# kick_line.net
KiCad netlist of a schematic drawn in EAGLE
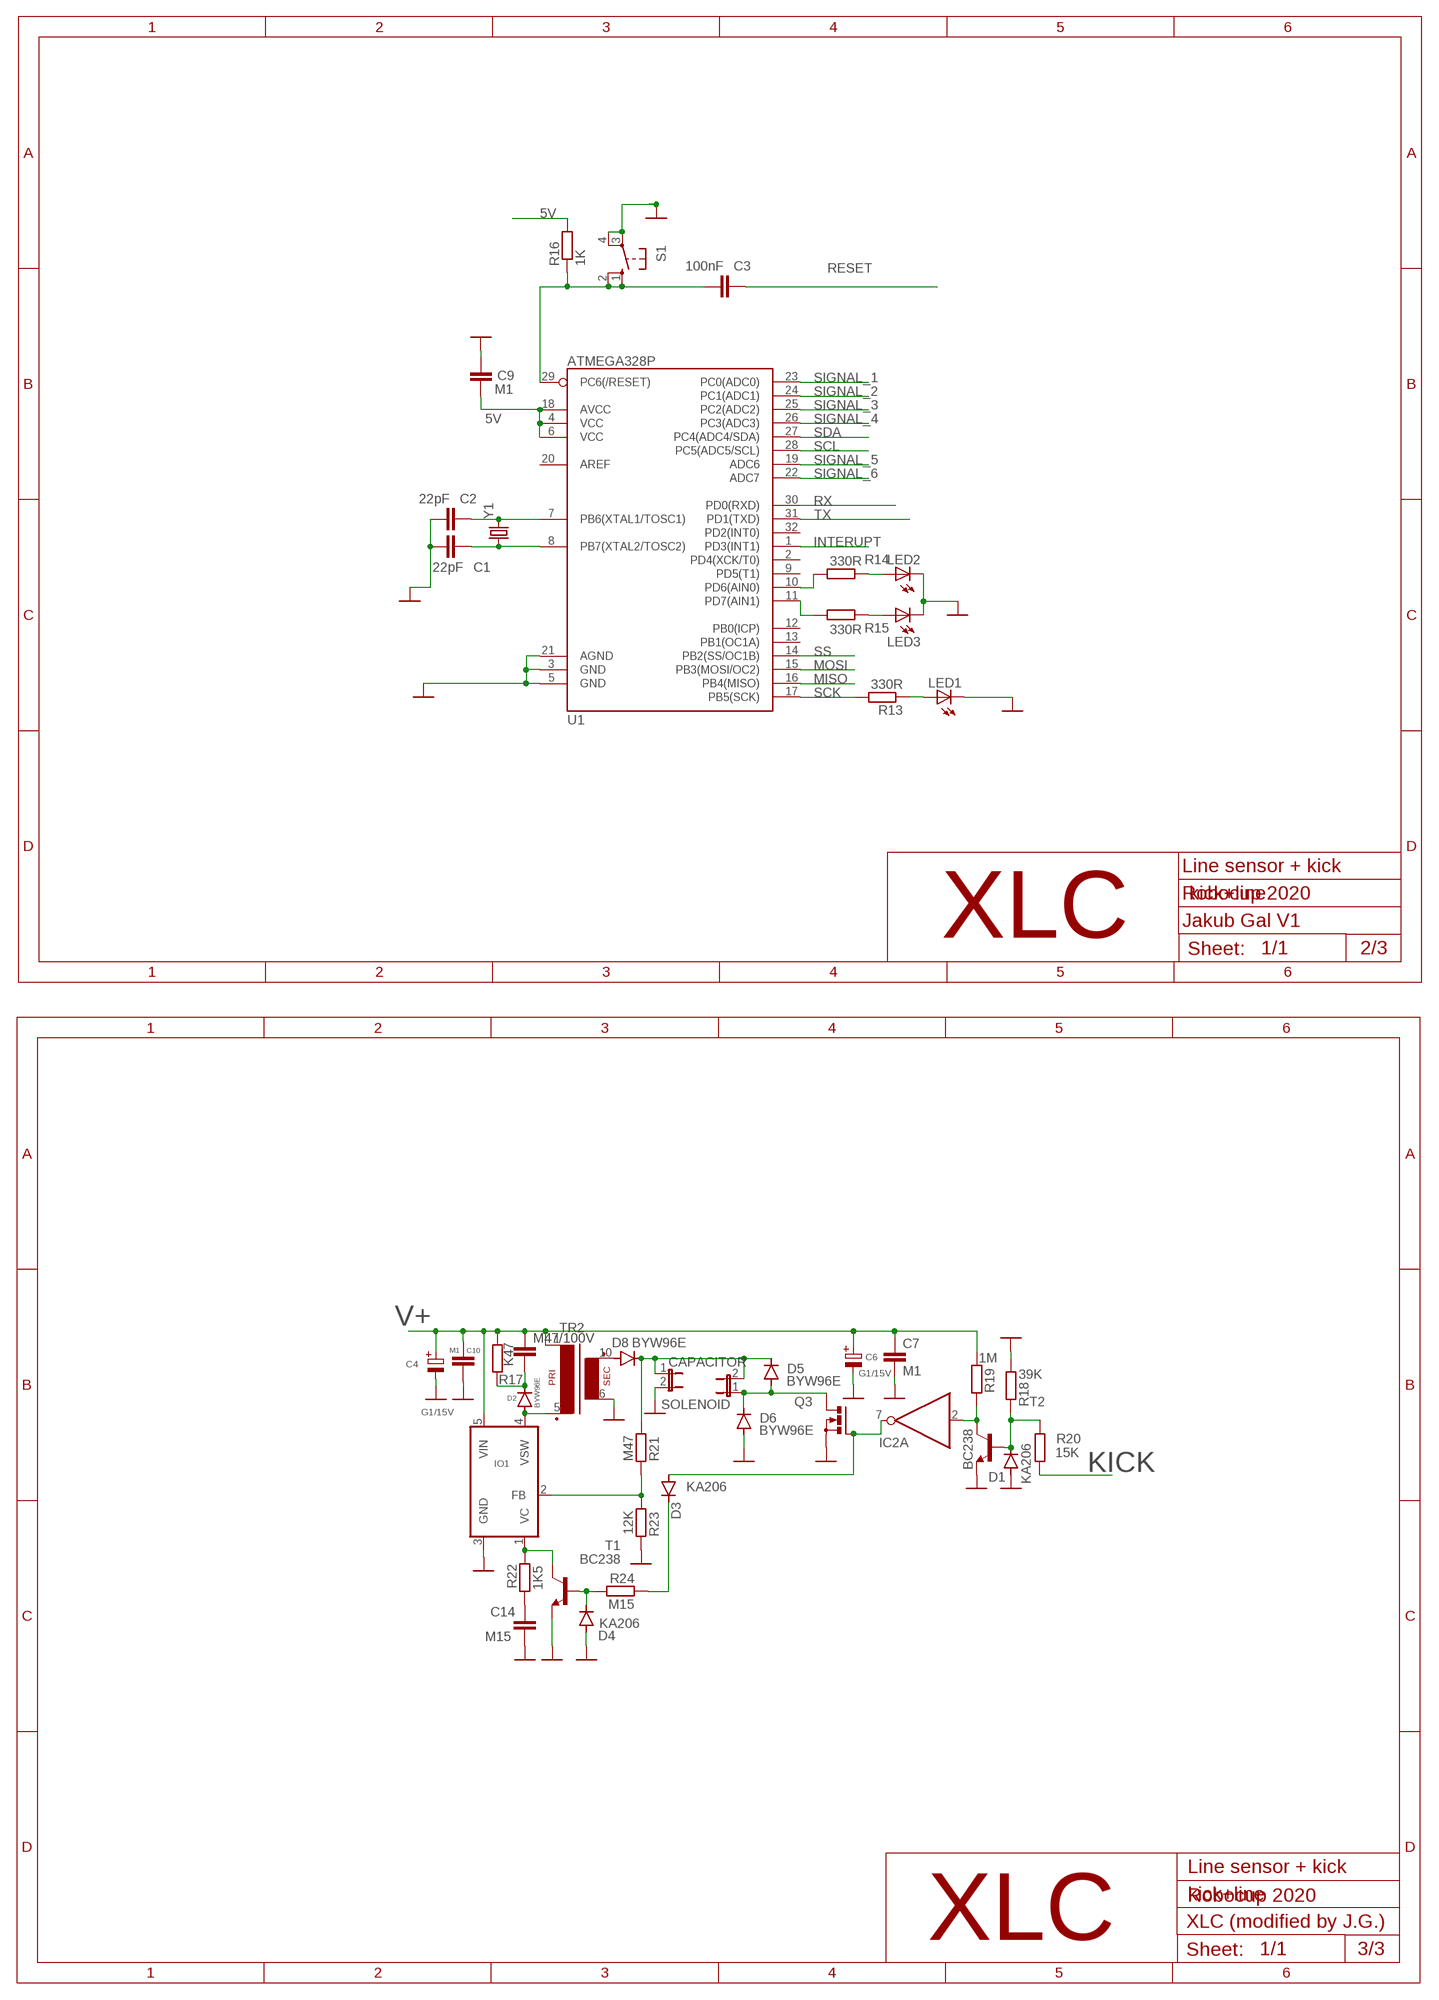
[diagram p0: schematic, sheet 1, part 1 of 2]
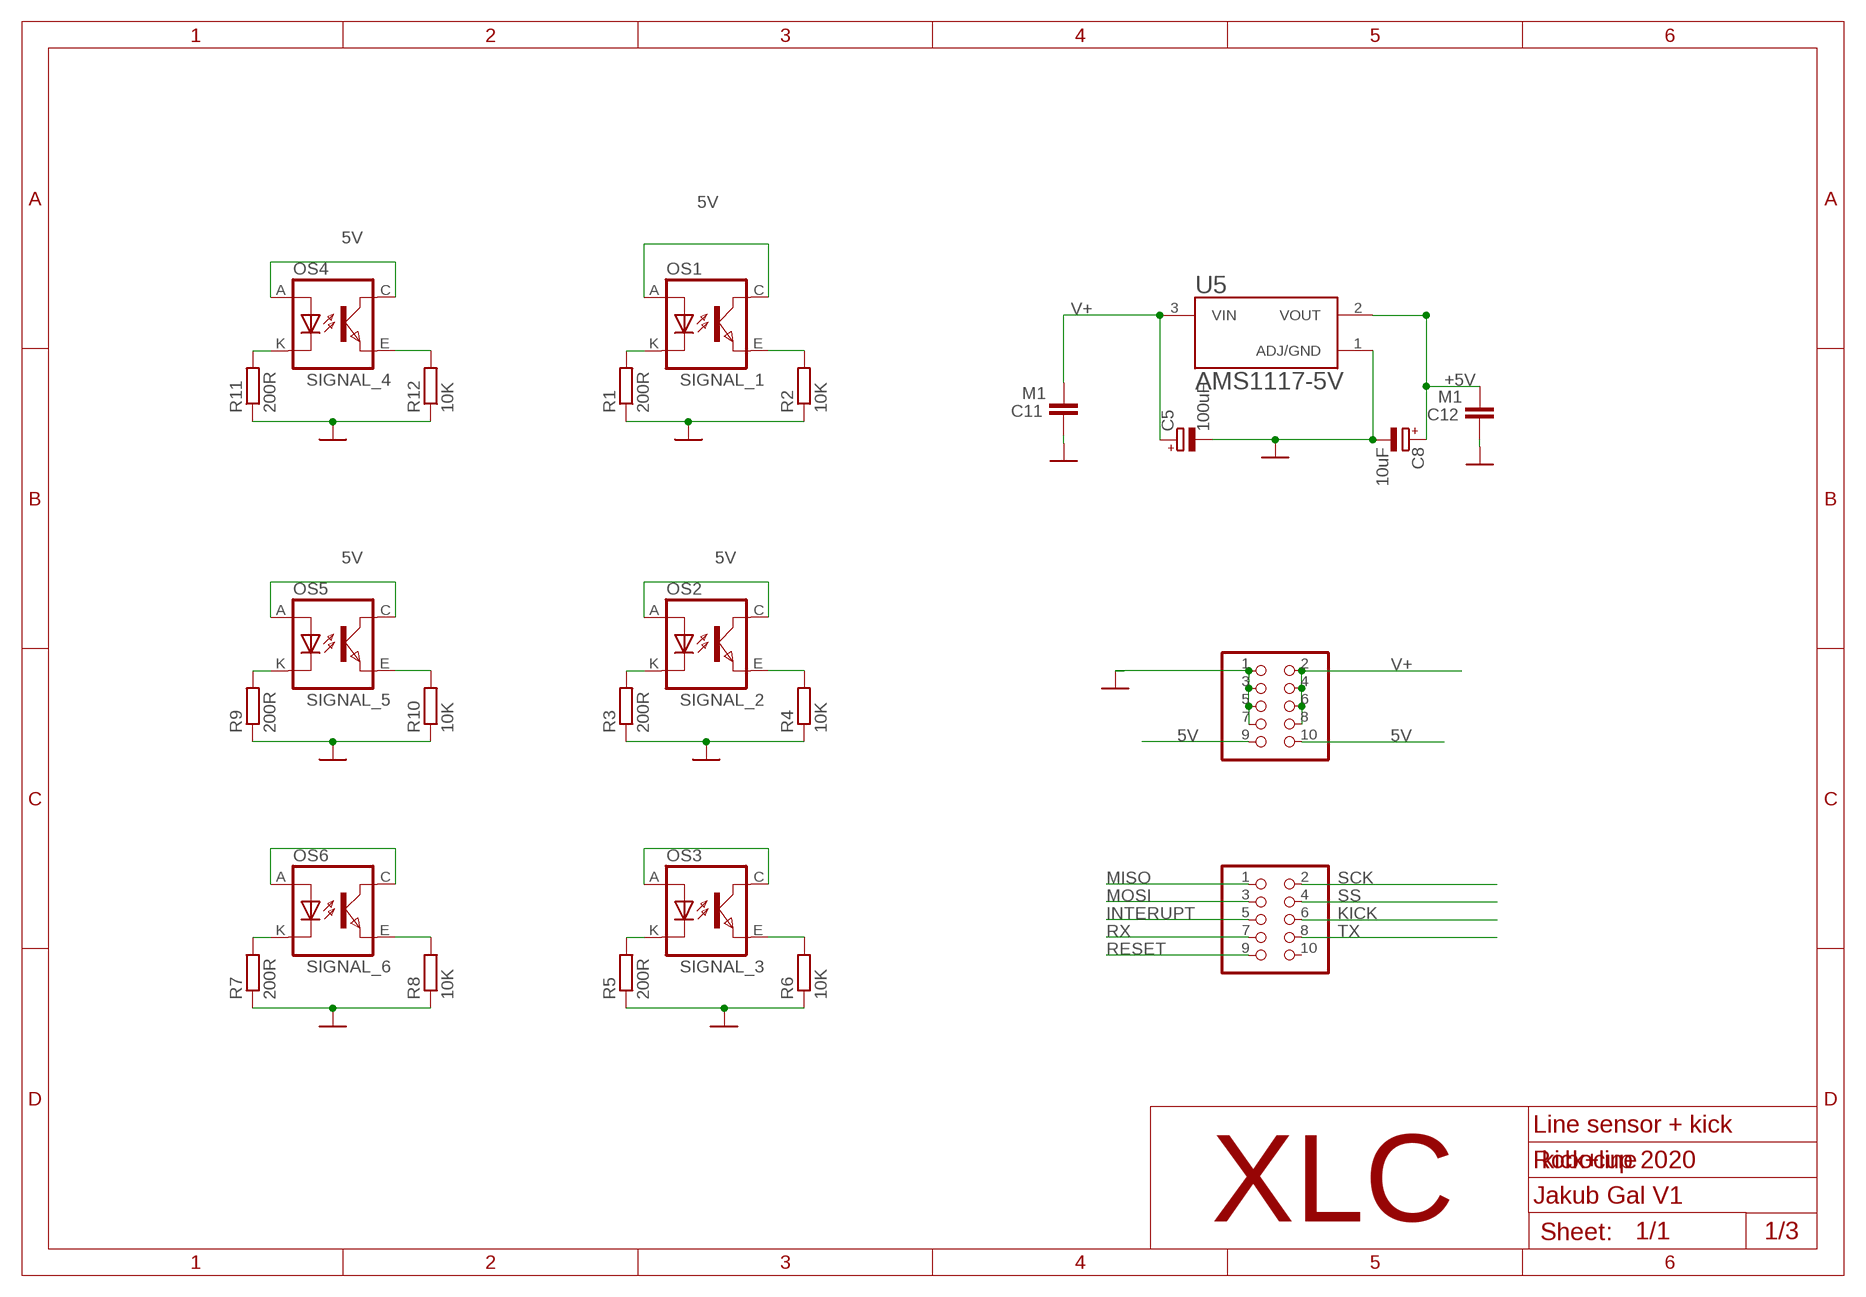
[diagram p1: schematic, sheet 1, part 2 of 2]

(export (version "E")
  (design (tool "Eeschema 10.0.6"))
  (components
    (comp (ref "C1")
      (value "22pF")
      (footprint "eagle-import:C0603")
      (libsource (lib "eagle-import") (part "C-EUC0603"))
    )
    (comp (ref "C2")
      (value "22pF")
      (footprint "eagle-import:C0603")
      (libsource (lib "eagle-import") (part "C-EUC0603"))
    )
    (comp (ref "C3")
      (value "100nF")
      (footprint "eagle-import:C0603")
      (libsource (lib "eagle-import") (part "C-EUC0603"))
    )
    (comp (ref "C4")
      (value "G1/15V")
      (footprint "eagle-import:E-2,5_7-RAD")
      (libsource (lib "eagle-import") (part "KOND-ELEKT-2,5/7"))
    )
    (comp (ref "C5")
      (value "100uF")
      (footprint "eagle-import:UD-6,3X7,7_NICHICON")
      (libsource (lib "eagle-import") (part "CPOL-EUUD-6,3X7,7"))
    )
    (comp (ref "C6")
      (value "G1/15V")
      (footprint "eagle-import:E-2,5_7-RAD")
      (libsource (lib "eagle-import") (part "KOND-ELEKT-2,5/7"))
    )
    (comp (ref "C7")
      (value "M1")
      (footprint "eagle-import:C0805K")
      (libsource (lib "eagle-import") (part "resistor_348_C-EUC0805K"))
    )
    (comp (ref "C8")
      (value "10uF")
      (footprint "eagle-import:UD-4X5,8_NICHICON")
      (libsource (lib "eagle-import") (part "CPOL-EUUD-4X5,8"))
    )
    (comp (ref "C9")
      (value "M1")
      (footprint "eagle-import:C0603")
      (libsource (lib "eagle-import") (part "C-EUC0603"))
    )
    (comp (ref "C10")
      (value "M1")
      (footprint "eagle-import:C0805K")
      (libsource (lib "eagle-import") (part "resistor_348_C-EUC0805K"))
    )
    (comp (ref "C11")
      (value "M1")
      (footprint "eagle-import:C0603")
      (libsource (lib "eagle-import") (part "C-EUC0603"))
    )
    (comp (ref "C12")
      (value "M1")
      (footprint "eagle-import:C0603")
      (libsource (lib "eagle-import") (part "C-EUC0603"))
    )
    (comp (ref "C14")
      (value "M15")
      (footprint "eagle-import:C0805K")
      (libsource (lib "eagle-import") (part "resistor_348_C-EUC0805K"))
    )
    (comp (ref "CAPACITOR")
      (value "JP1E")
      (footprint "eagle-import:JP1")
      (libsource (lib "eagle-import") (part "JP1E"))
    )
    (comp (ref "D1")
      (value "KA206")
      (footprint "eagle-import:D-7.5")
      (libsource (lib "eagle-import") (part "DIODE-D-7.5"))
    )
    (comp (ref "D2")
      (value "BYW96E")
      (footprint "eagle-import:SOD64-10")
      (libsource (lib "eagle-import") (part "BYW96"))
    )
    (comp (ref "D3")
      (value "KA206")
      (footprint "eagle-import:D-7.5")
      (libsource (lib "eagle-import") (part "DIODE-D-7.5"))
    )
    (comp (ref "D4")
      (value "KA206")
      (footprint "eagle-import:D-7.5")
      (libsource (lib "eagle-import") (part "DIODE-D-7.5"))
    )
    (comp (ref "D5")
      (value "BYW96E")
      (footprint "eagle-import:SOD64-10")
      (libsource (lib "eagle-import") (part "BYW96"))
    )
    (comp (ref "D6")
      (value "BYW96E")
      (footprint "eagle-import:SOD64-10")
      (libsource (lib "eagle-import") (part "BYW96"))
    )
    (comp (ref "D8")
      (value "BYW96E")
      (footprint "eagle-import:SOD64-10")
      (libsource (lib "eagle-import") (part "BYW96"))
    )
    (comp (ref "IC2")
      (value "MIC4423BM")
      (footprint "eagle-import:SO08")
      (libsource (lib "eagle-import") (part "MIC4423BM"))
    )
    (comp (ref "IO1")
      (value "LT1071V")
      (footprint "eagle-import:TO220-5P")
      (libsource (lib "eagle-import") (part "LT1071V"))
    )
    (comp (ref "JP2")
      (value "PINHD-2X5")
      (footprint "eagle-import:2X05")
      (libsource (lib "eagle-import") (part "PINHD-2X5"))
    )
    (comp (ref "JP3")
      (value "PINHD-2X5")
      (footprint "eagle-import:2X05")
      (libsource (lib "eagle-import") (part "PINHD-2X5"))
    )
    (comp (ref "LED1")
      (value "LEDCHIPLED_0603")
      (footprint "eagle-import:CHIPLED_0603")
      (libsource (lib "eagle-import") (part "LEDCHIPLED_0603"))
    )
    (comp (ref "LED2")
      (value "LEDCHIPLED_0603")
      (footprint "eagle-import:CHIPLED_0603")
      (libsource (lib "eagle-import") (part "LEDCHIPLED_0603"))
    )
    (comp (ref "LED3")
      (value "LEDCHIPLED_0603")
      (footprint "eagle-import:CHIPLED_0603")
      (libsource (lib "eagle-import") (part "LEDCHIPLED_0603"))
    )
    (comp (ref "M47/100V")
      (value "C-EUC0805K")
      (footprint "eagle-import:C0805K")
      (libsource (lib "eagle-import") (part "resistor_348_C-EUC0805K"))
    )
    (comp (ref "OS1")
      (value "TCRT5000")
      (footprint "eagle-import:TCRT5000")
      (libsource (lib "eagle-import") (part "TCRT5000"))
    )
    (comp (ref "OS2")
      (value "TCRT5000")
      (footprint "eagle-import:TCRT5000")
      (libsource (lib "eagle-import") (part "TCRT5000"))
    )
    (comp (ref "OS3")
      (value "TCRT5000")
      (footprint "eagle-import:TCRT5000")
      (libsource (lib "eagle-import") (part "TCRT5000"))
    )
    (comp (ref "OS4")
      (value "TCRT5000")
      (footprint "eagle-import:TCRT5000")
      (fields (field (name "SPICEPREFIX") "O"))
      (libsource (lib "eagle-import") (part "TCRT5000"))
    )
    (comp (ref "OS5")
      (value "TCRT5000")
      (footprint "eagle-import:TCRT5000")
      (libsource (lib "eagle-import") (part "TCRT5000"))
    )
    (comp (ref "OS6")
      (value "TCRT5000")
      (footprint "eagle-import:TCRT5000")
      (fields (field (name "SPICEPREFIX") "O"))
      (libsource (lib "eagle-import") (part "TCRT5000"))
    )
    (comp (ref "Q3")
      (value "PMOSFET_NTO220BV")
      (footprint "eagle-import:TO220BV")
      (libsource (lib "eagle-import") (part "PMOSFET_NTO220BV"))
    )
    (comp (ref "R1")
      (value "200R")
      (footprint "eagle-import:R0603")
      (libsource (lib "eagle-import") (part "R-EU_R0603"))
    )
    (comp (ref "R2")
      (value "10K")
      (footprint "eagle-import:R0603")
      (libsource (lib "eagle-import") (part "R-EU_R0603"))
    )
    (comp (ref "R3")
      (value "200R")
      (footprint "eagle-import:R0603")
      (libsource (lib "eagle-import") (part "R-EU_R0603"))
    )
    (comp (ref "R4")
      (value "10K")
      (footprint "eagle-import:R0603")
      (libsource (lib "eagle-import") (part "R-EU_R0603"))
    )
    (comp (ref "R5")
      (value "200R")
      (footprint "eagle-import:R0603")
      (libsource (lib "eagle-import") (part "R-EU_R0603"))
    )
    (comp (ref "R6")
      (value "10K")
      (footprint "eagle-import:R0603")
      (libsource (lib "eagle-import") (part "R-EU_R0603"))
    )
    (comp (ref "R7")
      (value "200R")
      (footprint "eagle-import:R0603")
      (libsource (lib "eagle-import") (part "R-EU_R0603"))
    )
    (comp (ref "R8")
      (value "10K")
      (footprint "eagle-import:R0603")
      (libsource (lib "eagle-import") (part "R-EU_R0603"))
    )
    (comp (ref "R9")
      (value "200R")
      (footprint "eagle-import:R0603")
      (libsource (lib "eagle-import") (part "R-EU_R0603"))
    )
    (comp (ref "R10")
      (value "10K")
      (footprint "eagle-import:R0603")
      (libsource (lib "eagle-import") (part "R-EU_R0603"))
    )
    (comp (ref "R11")
      (value "200R")
      (footprint "eagle-import:R0603")
      (libsource (lib "eagle-import") (part "R-EU_R0603"))
    )
    (comp (ref "R12")
      (value "10K")
      (footprint "eagle-import:R0603")
      (libsource (lib "eagle-import") (part "R-EU_R0603"))
    )
    (comp (ref "R13")
      (value "330R")
      (footprint "eagle-import:R0603")
      (libsource (lib "eagle-import") (part "R-EU_R0603"))
    )
    (comp (ref "R14")
      (value "330R")
      (footprint "eagle-import:R0603")
      (libsource (lib "eagle-import") (part "R-EU_R0603"))
    )
    (comp (ref "R15")
      (value "330R")
      (footprint "eagle-import:R0603")
      (libsource (lib "eagle-import") (part "R-EU_R0603"))
    )
    (comp (ref "R16")
      (value "1K")
      (footprint "eagle-import:R0603")
      (libsource (lib "eagle-import") (part "R-EU_R0603"))
    )
    (comp (ref "R17")
      (value "K47")
      (footprint "eagle-import:R0603")
      (libsource (lib "eagle-import") (part "resistor_348_R-EU_R0603"))
    )
    (comp (ref "R18")
      (value "39K")
      (footprint "eagle-import:R0603")
      (libsource (lib "eagle-import") (part "resistor_348_R-EU_R0603"))
    )
    (comp (ref "R19")
      (value "1M")
      (footprint "eagle-import:R0603")
      (libsource (lib "eagle-import") (part "resistor_348_R-EU_R0603"))
    )
    (comp (ref "R20")
      (value "15K")
      (footprint "eagle-import:R0603")
      (libsource (lib "eagle-import") (part "resistor_348_R-EU_R0603"))
    )
    (comp (ref "R21")
      (value "M47")
      (footprint "eagle-import:R0603")
      (libsource (lib "eagle-import") (part "resistor_348_R-EU_R0603"))
    )
    (comp (ref "R22")
      (value "1K5")
      (footprint "eagle-import:R0603")
      (libsource (lib "eagle-import") (part "resistor_348_R-EU_R0603"))
    )
    (comp (ref "R23")
      (value "12K")
      (footprint "eagle-import:R0603")
      (libsource (lib "eagle-import") (part "resistor_348_R-EU_R0603"))
    )
    (comp (ref "R24")
      (value "M15")
      (footprint "eagle-import:R0603")
      (libsource (lib "eagle-import") (part "resistor_348_R-EU_R0603"))
    )
    (comp (ref "S1")
      (value "10-XX")
      (footprint "eagle-import:B3F-10XX")
      (fields (field (name "MPN") "B3F-1000"))
      (libsource (lib "eagle-import") (part "10-XX"))
    )
    (comp (ref "SOLENOID")
      (value "JP1E")
      (footprint "eagle-import:JP1")
      (libsource (lib "eagle-import") (part "JP1E"))
    )
    (comp (ref "T1")
      (value "BC238")
      (footprint "eagle-import:TO92")
      (libsource (lib "eagle-import") (part "BC238"))
    )
    (comp (ref "T2")
      (value "BC238")
      (footprint "eagle-import:TO92")
      (libsource (lib "eagle-import") (part "BC238"))
    )
    (comp (ref "TR2")
      (value "TRAFO-E10-R\"\"")
      (footprint "eagle-import:TRAFO-EE17X20")
      (libsource (lib "eagle-import") (part "TRAFO-E10-R{dblquote}{dblquote}"))
    )
    (comp (ref "U1")
      (value "ATMEGA328P")
      (footprint "eagle-import:TQFP32-08")
      (libsource (lib "eagle-import") (part "ATMEGA328_SMT"))
    )
    (comp (ref "U5")
      (value "AMS1117-5V")
      (footprint "eagle-import:SOT229P700X180-4N")
      (fields (field (name "MF") "Advanced Monolithic Systems") (field (name "MP") "AMS1117-3.3"))
      (libsource (lib "eagle-import") (part "AMS1117-3.3"))
    )
    (comp (ref "Y1")
      (value "CRYSTALHC49US")
      (footprint "eagle-import:HC49US")
      (libsource (lib "eagle-import") (part "CRYSTALHC49US"))
    )
  )
  (nets
    (net (code "1") (name "/+5V") (class "Default")
      (node (ref "C12") (pin "1") (pinfunction "1_1") (pintype "passive"))
      (node (ref "C8") (pin "+") (pinfunction "+_+") (pintype "passive"))
      (node (ref "U5") (pin "2") (pinfunction "VOUT_2") (pintype "output"))
    )
    (net (code "2") (name "/5V") (class "Default")
      (node (ref "C9") (pin "1") (pinfunction "1_1") (pintype "passive"))
      (node (ref "JP3") (pin "10") (pinfunction "10_10") (pintype "passive"))
      (node (ref "JP3") (pin "9") (pinfunction "9_9") (pintype "passive"))
      (node (ref "OS1") (pin "A") (pinfunction "ANODE_A") (pintype "passive"))
      (node (ref "OS1") (pin "C") (pinfunction "COLLECTOR_C") (pintype "passive"))
      (node (ref "OS2") (pin "A") (pinfunction "ANODE_A") (pintype "passive"))
      (node (ref "OS2") (pin "C") (pinfunction "COLLECTOR_C") (pintype "passive"))
      (node (ref "OS3") (pin "A") (pinfunction "ANODE_A") (pintype "passive"))
      (node (ref "OS3") (pin "C") (pinfunction "COLLECTOR_C") (pintype "passive"))
      (node (ref "OS4") (pin "A") (pinfunction "ANODE_A") (pintype "passive"))
      (node (ref "OS4") (pin "C") (pinfunction "COLLECTOR_C") (pintype "passive"))
      (node (ref "OS5") (pin "A") (pinfunction "ANODE_A") (pintype "passive"))
      (node (ref "OS5") (pin "C") (pinfunction "COLLECTOR_C") (pintype "passive"))
      (node (ref "OS6") (pin "A") (pinfunction "ANODE_A") (pintype "passive"))
      (node (ref "OS6") (pin "C") (pinfunction "COLLECTOR_C") (pintype "passive"))
      (node (ref "R16") (pin "2") (pinfunction "2_2") (pintype "passive"))
      (node (ref "U1") (pin "18") (pinfunction "AVCC_18") (pintype "bidirectional"))
      (node (ref "U1") (pin "4") (pinfunction "VCC_4") (pintype "bidirectional"))
      (node (ref "U1") (pin "6") (pinfunction "VCC_6") (pintype "bidirectional"))
    )
    (net (code "3") (name "/INTERUPT") (class "Default")
      (node (ref "JP2") (pin "5") (pinfunction "5_5") (pintype "passive"))
      (node (ref "U1") (pin "1") (pinfunction "PD3(INT1)_1") (pintype "bidirectional"))
    )
    (net (code "4") (name "/KICK") (class "Default")
      (node (ref "JP2") (pin "6") (pinfunction "6_6") (pintype "passive"))
      (node (ref "R20") (pin "1") (pinfunction "1_1") (pintype "passive"))
    )
    (net (code "5") (name "/MISO") (class "Default")
      (node (ref "JP2") (pin "1") (pinfunction "1_1") (pintype "passive"))
      (node (ref "U1") (pin "16") (pinfunction "PB4(MISO)_16") (pintype "bidirectional"))
    )
    (net (code "6") (name "/MOSI") (class "Default")
      (node (ref "JP2") (pin "3") (pinfunction "3_3") (pintype "passive"))
      (node (ref "U1") (pin "15") (pinfunction "PB3(MOSI/OC2)_15") (pintype "bidirectional"))
    )
    (net (code "7") (name "/RESET") (class "Default")
      (node (ref "C3") (pin "2") (pinfunction "2_2") (pintype "passive"))
      (node (ref "JP2") (pin "9") (pinfunction "9_9") (pintype "passive"))
    )
    (net (code "8") (name "/RX") (class "Default")
      (node (ref "JP2") (pin "7") (pinfunction "7_7") (pintype "passive"))
      (node (ref "U1") (pin "30") (pinfunction "PD0(RXD)_30") (pintype "bidirectional"))
    )
    (net (code "9") (name "/SCK") (class "Default")
      (node (ref "JP2") (pin "2") (pinfunction "2_2") (pintype "passive"))
      (node (ref "R13") (pin "2") (pinfunction "2_2") (pintype "passive"))
      (node (ref "U1") (pin "17") (pinfunction "PB5(SCK)_17") (pintype "bidirectional"))
    )
    (net (code "10") (name "/SCL") (class "Default")
      (node (ref "U1") (pin "28") (pinfunction "PC5(ADC5/SCL)_28") (pintype "bidirectional"))
    )
    (net (code "11") (name "/SDA") (class "Default")
      (node (ref "U1") (pin "27") (pinfunction "PC4(ADC4/SDA)_27") (pintype "bidirectional"))
    )
    (net (code "12") (name "/SIGNAL_1") (class "Default")
      (node (ref "OS1") (pin "E") (pinfunction "EMITTER_E") (pintype "passive"))
      (node (ref "R2") (pin "2") (pinfunction "2_2") (pintype "passive"))
      (node (ref "U1") (pin "23") (pinfunction "PC0(ADC0)_23") (pintype "bidirectional"))
    )
    (net (code "13") (name "/SIGNAL_2") (class "Default")
      (node (ref "OS2") (pin "E") (pinfunction "EMITTER_E") (pintype "passive"))
      (node (ref "R4") (pin "2") (pinfunction "2_2") (pintype "passive"))
      (node (ref "U1") (pin "24") (pinfunction "PC1(ADC1)_24") (pintype "bidirectional"))
    )
    (net (code "14") (name "/SIGNAL_3") (class "Default")
      (node (ref "OS3") (pin "E") (pinfunction "EMITTER_E") (pintype "passive"))
      (node (ref "R6") (pin "2") (pinfunction "2_2") (pintype "passive"))
      (node (ref "U1") (pin "25") (pinfunction "PC2(ADC2)_25") (pintype "bidirectional"))
    )
    (net (code "15") (name "/SIGNAL_4") (class "Default")
      (node (ref "OS4") (pin "E") (pinfunction "EMITTER_E") (pintype "passive"))
      (node (ref "R12") (pin "2") (pinfunction "2_2") (pintype "passive"))
      (node (ref "U1") (pin "26") (pinfunction "PC3(ADC3)_26") (pintype "bidirectional"))
    )
    (net (code "16") (name "/SIGNAL_5") (class "Default")
      (node (ref "OS5") (pin "E") (pinfunction "EMITTER_E") (pintype "passive"))
      (node (ref "R10") (pin "2") (pinfunction "2_2") (pintype "passive"))
      (node (ref "U1") (pin "19") (pinfunction "ADC6_19") (pintype "bidirectional"))
    )
    (net (code "17") (name "/SIGNAL_6") (class "Default")
      (node (ref "OS6") (pin "E") (pinfunction "EMITTER_E") (pintype "passive"))
      (node (ref "R8") (pin "2") (pinfunction "2_2") (pintype "passive"))
      (node (ref "U1") (pin "22") (pinfunction "ADC7_22") (pintype "bidirectional"))
    )
    (net (code "18") (name "/SS") (class "Default")
      (node (ref "JP2") (pin "4") (pinfunction "4_4") (pintype "passive"))
      (node (ref "U1") (pin "14") (pinfunction "PB2(SS/OC1B)_14") (pintype "bidirectional"))
    )
    (net (code "19") (name "/TX") (class "Default")
      (node (ref "JP2") (pin "8") (pinfunction "8_8") (pintype "passive"))
      (node (ref "U1") (pin "31") (pinfunction "PD1(TXD)_31") (pintype "bidirectional"))
    )
    (net (code "20") (name "/V+") (class "Default")
      (node (ref "C10") (pin "1") (pinfunction "1_1") (pintype "passive"))
      (node (ref "C11") (pin "1") (pinfunction "1_1") (pintype "passive"))
      (node (ref "C4") (pin "+") (pinfunction "+_+") (pintype "passive"))
      (node (ref "C5") (pin "+") (pinfunction "+_+") (pintype "passive"))
      (node (ref "C6") (pin "+") (pinfunction "+_+") (pintype "passive"))
      (node (ref "C7") (pin "1") (pinfunction "1_1") (pintype "passive"))
      (node (ref "IO1") (pin "5") (pinfunction "VIN_5") (pintype "power_in"))
      (node (ref "JP3") (pin "2") (pinfunction "2_2") (pintype "passive"))
      (node (ref "JP3") (pin "4") (pinfunction "4_4") (pintype "passive"))
      (node (ref "JP3") (pin "6") (pinfunction "6_6") (pintype "passive"))
      (node (ref "JP3") (pin "8") (pinfunction "8_8") (pintype "passive"))
      (node (ref "M47/100V") (pin "1") (pinfunction "1_1") (pintype "passive"))
      (node (ref "R17") (pin "1") (pinfunction "1_1") (pintype "passive"))
      (node (ref "R19") (pin "2") (pinfunction "2_2") (pintype "passive"))
      (node (ref "TR2") (pin "1") (pinfunction "1_1") (pintype "passive"))
      (node (ref "U5") (pin "3") (pinfunction "VIN_3") (pintype "input"))
    )
    (net (code "21") (name "GND") (class "Default")
      (node (ref "C1") (pin "1") (pinfunction "1_1") (pintype "passive"))
      (node (ref "C10") (pin "2") (pinfunction "2_2") (pintype "passive"))
      (node (ref "C11") (pin "2") (pinfunction "2_2") (pintype "passive"))
      (node (ref "C12") (pin "2") (pinfunction "2_2") (pintype "passive"))
      (node (ref "C14") (pin "2") (pinfunction "2_2") (pintype "passive"))
      (node (ref "C2") (pin "1") (pinfunction "1_1") (pintype "passive"))
      (node (ref "C4") (pin "-") (pinfunction "-_-") (pintype "passive"))
      (node (ref "C5") (pin "-") (pinfunction "-_-") (pintype "passive"))
      (node (ref "C6") (pin "-") (pinfunction "-_-") (pintype "passive"))
      (node (ref "C7") (pin "2") (pinfunction "2_2") (pintype "passive"))
      (node (ref "C8") (pin "-") (pinfunction "-_-") (pintype "passive"))
      (node (ref "C9") (pin "2") (pinfunction "2_2") (pintype "passive"))
      (node (ref "CAPACITOR") (pin "2") (pinfunction "2_2") (pintype "passive"))
      (node (ref "D1") (pin "A") (pinfunction "A_A") (pintype "passive"))
      (node (ref "D4") (pin "A") (pinfunction "A_A") (pintype "passive"))
      (node (ref "D6") (pin "A") (pinfunction "A_A") (pintype "passive"))
      (node (ref "IO1") (pin "3") (pinfunction "GND_3") (pintype "power_in"))
      (node (ref "JP3") (pin "1") (pinfunction "1_1") (pintype "passive"))
      (node (ref "JP3") (pin "3") (pinfunction "3_3") (pintype "passive"))
      (node (ref "JP3") (pin "5") (pinfunction "5_5") (pintype "passive"))
      (node (ref "JP3") (pin "7") (pinfunction "7_7") (pintype "passive"))
      (node (ref "LED1") (pin "C") (pinfunction "C_C") (pintype "passive"))
      (node (ref "LED2") (pin "C") (pinfunction "C_C") (pintype "passive"))
      (node (ref "LED3") (pin "C") (pinfunction "C_C") (pintype "passive"))
      (node (ref "Q3") (pin "S") (pinfunction "S_S") (pintype "passive"))
      (node (ref "R1") (pin "1") (pinfunction "1_1") (pintype "passive"))
      (node (ref "R10") (pin "1") (pinfunction "1_1") (pintype "passive"))
      (node (ref "R11") (pin "1") (pinfunction "1_1") (pintype "passive"))
      (node (ref "R12") (pin "1") (pinfunction "1_1") (pintype "passive"))
      (node (ref "R18") (pin "2") (pinfunction "2_2") (pintype "passive"))
      (node (ref "R2") (pin "1") (pinfunction "1_1") (pintype "passive"))
      (node (ref "R23") (pin "1") (pinfunction "1_1") (pintype "passive"))
      (node (ref "R3") (pin "1") (pinfunction "1_1") (pintype "passive"))
      (node (ref "R4") (pin "1") (pinfunction "1_1") (pintype "passive"))
      (node (ref "R5") (pin "1") (pinfunction "1_1") (pintype "passive"))
      (node (ref "R6") (pin "1") (pinfunction "1_1") (pintype "passive"))
      (node (ref "R7") (pin "1") (pinfunction "1_1") (pintype "passive"))
      (node (ref "R8") (pin "1") (pinfunction "1_1") (pintype "passive"))
      (node (ref "R9") (pin "1") (pinfunction "1_1") (pintype "passive"))
      (node (ref "S1") (pin "3") (pinfunction "P_3") (pintype "passive"))
      (node (ref "S1") (pin "4") (pinfunction "P1_4") (pintype "passive"))
      (node (ref "T1") (pin "1") (pinfunction "E_1") (pintype "passive"))
      (node (ref "T2") (pin "1") (pinfunction "E_1") (pintype "passive"))
      (node (ref "TR2") (pin "6") (pinfunction "3_6") (pintype "passive"))
      (node (ref "U1") (pin "21") (pinfunction "AGND_21") (pintype "bidirectional"))
      (node (ref "U1") (pin "3") (pinfunction "GND_3") (pintype "bidirectional"))
      (node (ref "U1") (pin "5") (pinfunction "GND_5") (pintype "bidirectional"))
      (node (ref "U5") (pin "1") (pinfunction "ADJ/GND_1") (pintype "power_in"))
    )
    (net (code "22") (name "Net-(C14-Pad1)") (class "Default")
      (node (ref "C14") (pin "1") (pinfunction "1_1") (pintype "passive"))
      (node (ref "R22") (pin "2") (pinfunction "2_2") (pintype "passive"))
    )
    (net (code "23") (name "Net-(CAPACITOR-Pad1)") (class "Default")
      (node (ref "CAPACITOR") (pin "1") (pinfunction "1_1") (pintype "passive"))
      (node (ref "D5") (pin "C") (pinfunction "C_C") (pintype "passive"))
      (node (ref "D8") (pin "C") (pinfunction "C_C") (pintype "passive"))
      (node (ref "R21") (pin "2") (pinfunction "2_2") (pintype "passive"))
      (node (ref "SOLENOID") (pin "2") (pinfunction "2_2") (pintype "passive"))
    )
    (net (code "24") (name "Net-(D2-PadC)") (class "Default")
      (node (ref "D2") (pin "C") (pinfunction "C_C") (pintype "passive"))
      (node (ref "M47/100V") (pin "2") (pinfunction "2_2") (pintype "passive"))
      (node (ref "R17") (pin "2") (pinfunction "2_2") (pintype "passive"))
    )
    (net (code "25") (name "Net-(D3-PadC)") (class "Default")
      (node (ref "D3") (pin "C") (pinfunction "C_C") (pintype "passive"))
      (node (ref "R24") (pin "1") (pinfunction "1_1") (pintype "passive"))
    )
    (net (code "26") (name "Net-(D5-PadA)") (class "Default")
      (node (ref "D5") (pin "A") (pinfunction "A_A") (pintype "passive"))
      (node (ref "D6") (pin "C") (pinfunction "C_C") (pintype "passive"))
      (node (ref "Q3") (pin "D") (pinfunction "D_D") (pintype "passive"))
      (node (ref "SOLENOID") (pin "1") (pinfunction "1_1") (pintype "passive"))
    )
    (net (code "27") (name "Net-(IC2A-IN)") (class "Default")
      (node (ref "IC2") (pin "2") (pinfunction "IN_2") (pintype "input"))
      (node (ref "R19") (pin "1") (pinfunction "1_1") (pintype "passive"))
      (node (ref "T2") (pin "3") (pinfunction "C_3") (pintype "passive"))
    )
    (net (code "28") (name "Net-(IC2A-OUT)") (class "Default")
      (node (ref "D3") (pin "A") (pinfunction "A_A") (pintype "passive"))
      (node (ref "IC2") (pin "7") (pinfunction "OUT_7") (pintype "output"))
      (node (ref "Q3") (pin "G") (pinfunction "G_G") (pintype "passive"))
    )
    (net (code "29") (name "Net-(IO1-FB)") (class "Default")
      (node (ref "IO1") (pin "2") (pinfunction "FB_2") (pintype "input"))
      (node (ref "R21") (pin "1") (pinfunction "1_1") (pintype "passive"))
      (node (ref "R23") (pin "2") (pinfunction "2_2") (pintype "passive"))
    )
    (net (code "30") (name "Net-(IO1-VC)") (class "Default")
      (node (ref "IO1") (pin "1") (pinfunction "VC_1") (pintype "input"))
      (node (ref "R22") (pin "1") (pinfunction "1_1") (pintype "passive"))
      (node (ref "T1") (pin "3") (pinfunction "C_3") (pintype "passive"))
    )
    (net (code "31") (name "Net-(IO1-VSW)") (class "Default")
      (node (ref "D2") (pin "A") (pinfunction "A_A") (pintype "passive"))
      (node (ref "IO1") (pin "4") (pinfunction "VSW_4") (pintype "output"))
      (node (ref "TR2") (pin "5") (pinfunction "2_5") (pintype "passive"))
    )
    (net (code "32") (name "Net-(LED1-PadA)") (class "Default")
      (node (ref "LED1") (pin "A") (pinfunction "A_A") (pintype "passive"))
      (node (ref "R13") (pin "1") (pinfunction "1_1") (pintype "passive"))
    )
    (net (code "33") (name "Net-(LED2-PadA)") (class "Default")
      (node (ref "LED2") (pin "A") (pinfunction "A_A") (pintype "passive"))
      (node (ref "R14") (pin "1") (pinfunction "1_1") (pintype "passive"))
    )
    (net (code "34") (name "Net-(LED3-PadA)") (class "Default")
      (node (ref "LED3") (pin "A") (pinfunction "A_A") (pintype "passive"))
      (node (ref "R15") (pin "1") (pinfunction "1_1") (pintype "passive"))
    )
    (net (code "35") (name "Net-(OS1-CATHODE)") (class "Default")
      (node (ref "OS1") (pin "K") (pinfunction "CATHODE_K") (pintype "passive"))
      (node (ref "R1") (pin "2") (pinfunction "2_2") (pintype "passive"))
    )
    (net (code "36") (name "Net-(OS2-CATHODE)") (class "Default")
      (node (ref "OS2") (pin "K") (pinfunction "CATHODE_K") (pintype "passive"))
      (node (ref "R3") (pin "2") (pinfunction "2_2") (pintype "passive"))
    )
    (net (code "37") (name "Net-(OS3-CATHODE)") (class "Default")
      (node (ref "OS3") (pin "K") (pinfunction "CATHODE_K") (pintype "passive"))
      (node (ref "R5") (pin "2") (pinfunction "2_2") (pintype "passive"))
    )
    (net (code "38") (name "Net-(OS4-CATHODE)") (class "Default")
      (node (ref "OS4") (pin "K") (pinfunction "CATHODE_K") (pintype "passive"))
      (node (ref "R11") (pin "2") (pinfunction "2_2") (pintype "passive"))
    )
    (net (code "39") (name "Net-(OS5-CATHODE)") (class "Default")
      (node (ref "OS5") (pin "K") (pinfunction "CATHODE_K") (pintype "passive"))
      (node (ref "R9") (pin "2") (pinfunction "2_2") (pintype "passive"))
    )
    (net (code "40") (name "Net-(OS6-CATHODE)") (class "Default")
      (node (ref "OS6") (pin "K") (pinfunction "CATHODE_K") (pintype "passive"))
      (node (ref "R7") (pin "2") (pinfunction "2_2") (pintype "passive"))
    )
    (net (code "41") (name "Net-(S1-S)") (class "Default")
      (node (ref "C3") (pin "1") (pinfunction "1_1") (pintype "passive"))
      (node (ref "R16") (pin "1") (pinfunction "1_1") (pintype "passive"))
      (node (ref "S1") (pin "1") (pinfunction "S_1") (pintype "passive"))
      (node (ref "S1") (pin "2") (pinfunction "S1_2") (pintype "passive"))
      (node (ref "U1") (pin "29") (pinfunction "PC6(/RESET)_29") (pintype "bidirectional"))
    )
    (net (code "42") (name "Net-(T1-B)") (class "Default")
      (node (ref "D4") (pin "C") (pinfunction "C_C") (pintype "passive"))
      (node (ref "R24") (pin "2") (pinfunction "2_2") (pintype "passive"))
      (node (ref "T1") (pin "2") (pinfunction "B_2") (pintype "passive"))
    )
    (net (code "43") (name "Net-(T2-B)") (class "Default")
      (node (ref "D1") (pin "C") (pinfunction "C_C") (pintype "passive"))
      (node (ref "R18") (pin "1") (pinfunction "1_1") (pintype "passive"))
      (node (ref "R20") (pin "2") (pinfunction "2_2") (pintype "passive"))
      (node (ref "T2") (pin "2") (pinfunction "B_2") (pintype "passive"))
    )
    (net (code "44") (name "Net-(TR2-4)") (class "Default")
      (node (ref "D8") (pin "A") (pinfunction "A_A") (pintype "passive"))
      (node (ref "TR2") (pin "10") (pinfunction "4_10") (pintype "passive"))
    )
    (net (code "45") (name "Net-(U1-PB6(XTAL1{slash}TOSC1))") (class "Default")
      (node (ref "C2") (pin "2") (pinfunction "2_2") (pintype "passive"))
      (node (ref "U1") (pin "7") (pinfunction "PB6(XTAL1/TOSC1)_7") (pintype "bidirectional"))
      (node (ref "Y1") (pin "2") (pinfunction "2_2") (pintype "passive"))
    )
    (net (code "46") (name "Net-(U1-PB7(XTAL2{slash}TOSC2))") (class "Default")
      (node (ref "C1") (pin "2") (pinfunction "2_2") (pintype "passive"))
      (node (ref "U1") (pin "8") (pinfunction "PB7(XTAL2/TOSC2)_8") (pintype "bidirectional"))
      (node (ref "Y1") (pin "1") (pinfunction "1_1") (pintype "passive"))
    )
    (net (code "47") (name "Net-(U1-PD6(AIN0))") (class "Default")
      (node (ref "R14") (pin "2") (pinfunction "2_2") (pintype "passive"))
      (node (ref "U1") (pin "10") (pinfunction "PD6(AIN0)_10") (pintype "bidirectional"))
    )
    (net (code "48") (name "Net-(U1-PD7(AIN1))") (class "Default")
      (node (ref "R15") (pin "2") (pinfunction "2_2") (pintype "passive"))
      (node (ref "U1") (pin "11") (pinfunction "PD7(AIN1)_11") (pintype "bidirectional"))
    )
    (net (code "49") (name "unconnected-(JP2-Pad10)") (class "Default")
      (node (ref "JP2") (pin "10") (pinfunction "10_10") (pintype "passive"))
    )
    (net (code "50") (name "unconnected-(U1-AREF-Pad20)") (class "Default")
      (node (ref "U1") (pin "20") (pinfunction "AREF_20") (pintype "bidirectional"))
    )
    (net (code "51") (name "unconnected-(U1-PB0(ICP)-Pad12)") (class "Default")
      (node (ref "U1") (pin "12") (pinfunction "PB0(ICP)_12") (pintype "bidirectional"))
    )
    (net (code "52") (name "unconnected-(U1-PB1(OC1A)-Pad13)") (class "Default")
      (node (ref "U1") (pin "13") (pinfunction "PB1(OC1A)_13") (pintype "bidirectional"))
    )
    (net (code "53") (name "unconnected-(U1-PD2(INT0)-Pad32)") (class "Default")
      (node (ref "U1") (pin "32") (pinfunction "PD2(INT0)_32") (pintype "bidirectional"))
    )
    (net (code "54") (name "unconnected-(U1-PD4(XCK{slash}T0)-Pad2)") (class "Default")
      (node (ref "U1") (pin "2") (pinfunction "PD4(XCK/T0)_2") (pintype "bidirectional"))
    )
    (net (code "55") (name "unconnected-(U1-PD5(T1)-Pad9)") (class "Default")
      (node (ref "U1") (pin "9") (pinfunction "PD5(T1)_9") (pintype "bidirectional"))
    )
  )
)
